# capteur_couple.net
KiCad netlist of a schematic drawn in Altium Designer
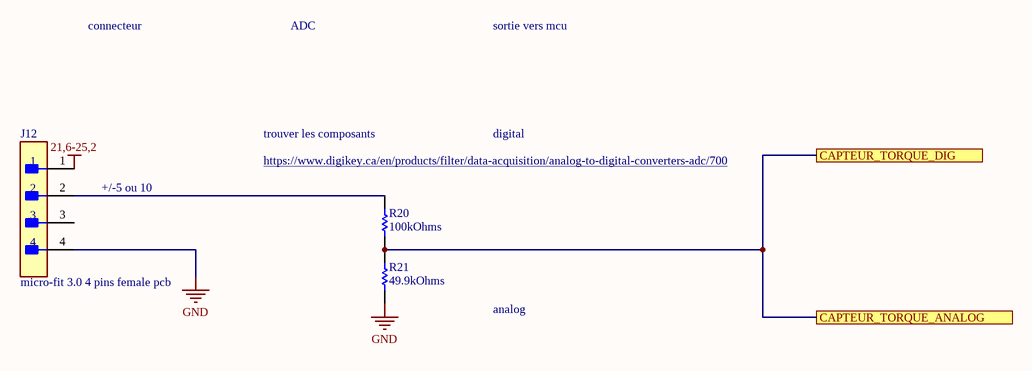
[diagram p0: capteur_couple.SchDoc]

(export (version "E")
  (design (tool "Eeschema 10.0.6"))
  (components
    (comp (ref "J12")
      (value "micro-fit 3.0 4 pins female pcb")
      (footprint "FP-43045-0400-MFG")
      (description "MOLEX 43045-0400 Header, Dual Row, 90°, 4p, Tin Plating Snap-in Peg PCB Lock, GW Compatible")
      (fields (field (name "MANUFACTURER") "Molex") (field (name "MANUFACTURER PART NUMBER") "43045-0400"))
      (libsource (lib "chinook_lib_symbol_rotor") (part "430450400"))
    )
    (comp (ref "R20")
      (value "100kOhms")
      (footprint "RESC1005X40X25NL05T10")
      (description "SMD Chip Resistor, 100 kOhm, ± 1%, 63 mW, 0402 [1005 Metric], Thick Film, General Purpose")
      (fields
        (field (name "MANUFACTURER") "Yageo")
        (field (name "MANUFACTURER PART NUMBER") "RC0402FR-07100KL")
      )
      (libsource (lib "chinook_lib_symbol_rotor") (part "RC0402FR-07100KL"))
    )
    (comp (ref "R21")
      (value "49.9kOhms")
      (footprint "RESC1005X40X25LL05T10")
      (libsource (lib "chinook_lib_symbol_rotor") (part "RC0402FR-0749K9L"))
    )
  )
  (nets
    (net (code "1") (name "/CAPTEUR_TORQUE_ANALOG") (class "Default")
      (node (ref "R20") (pin "1") (pinfunction "1_1") (pintype "passive"))
      (node (ref "R21") (pin "2") (pinfunction "2_2") (pintype "passive"))
    )
    (net (code "2") (name "21,6-25,2") (class "Default")
      (node (ref "J12") (pin "1") (pinfunction "1_1") (pintype "passive"))
    )
    (net (code "3") (name "GND") (class "Default")
      (node (ref "J12") (pin "4") (pinfunction "4_4") (pintype "passive"))
      (node (ref "R21") (pin "1") (pinfunction "1_1") (pintype "passive"))
    )
    (net (code "4") (name "Net-(J12-Pad2)") (class "Default")
      (node (ref "J12") (pin "2") (pinfunction "2_2") (pintype "passive"))
      (node (ref "R20") (pin "2") (pinfunction "2_2") (pintype "passive"))
    )
    (net (code "5") (name "unconnected-(J12-Pad3)") (class "Default")
      (node (ref "J12") (pin "3") (pinfunction "3_3") (pintype "passive"))
    )
  )
)
